# 24V_PWS.net
KiCad netlist of a schematic drawn in EAGLE
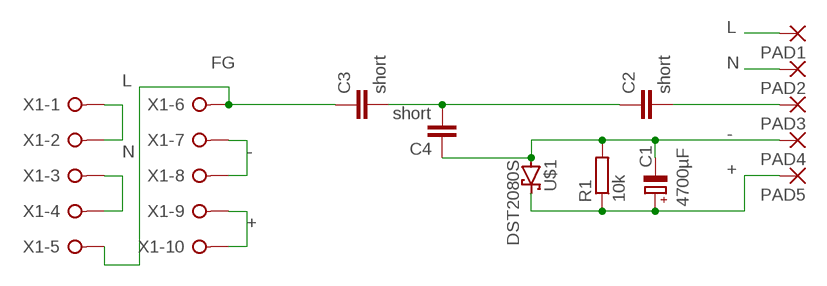
[diagram p0: schematic, sheet 1]

(export (version "E")
  (design (tool "Eeschema 10.0.6"))
  (components
    (comp (ref "C1")
      (value "4700µF")
      (footprint "eagle-import:E7,5-18")
      (libsource (lib "eagle-import") (part "CPOL-EUE7.5-18"))
    )
    (comp (ref "C2")
      (value "short")
      (footprint "eagle-import:C1206")
      (libsource (lib "eagle-import") (part "C-EUC1206"))
    )
    (comp (ref "C3")
      (value "short")
      (footprint "eagle-import:C1206")
      (libsource (lib "eagle-import") (part "C-EUC1206"))
    )
    (comp (ref "C4")
      (value "short")
      (footprint "eagle-import:C1206")
      (libsource (lib "eagle-import") (part "C-EUC1206"))
    )
    (comp (ref "PAD1")
      (value "SMD5")
      (footprint "eagle-import:SMD2,54-5,08")
      (libsource (lib "eagle-import") (part "SMD5"))
    )
    (comp (ref "PAD2")
      (value "SMD5")
      (footprint "eagle-import:SMD2,54-5,08")
      (libsource (lib "eagle-import") (part "SMD5"))
    )
    (comp (ref "PAD3")
      (value "SMD5")
      (footprint "eagle-import:SMD2,54-5,08")
      (libsource (lib "eagle-import") (part "SMD5"))
    )
    (comp (ref "PAD4")
      (value "SMD5")
      (footprint "eagle-import:SMD2,54-5,08")
      (libsource (lib "eagle-import") (part "SMD5"))
    )
    (comp (ref "PAD5")
      (value "SMD5")
      (footprint "eagle-import:SMD2,54-5,08")
      (libsource (lib "eagle-import") (part "SMD5"))
    )
    (comp (ref "R1")
      (value "10k")
      (footprint "eagle-import:R2012")
      (libsource (lib "eagle-import") (part "R-EU_R2012"))
    )
    (comp (ref "U$1")
      (value "DST2080S")
      (footprint "eagle-import:TO-277B")
      (libsource (lib "eagle-import") (part "DST2080S"))
    )
    (comp (ref "X1")
      (value "W237-10P")
      (footprint "eagle-import:W237-10P")
      (libsource (lib "eagle-import") (part "W237-10P"))
    )
  )
  (nets
    (net (code "1") (name "/+") (class "Default")
      (node (ref "C1") (pin "+") (pinfunction "+_+") (pintype "passive"))
      (node (ref "PAD5") (pin "1") (pinfunction "P_1") (pintype "passive"))
      (node (ref "R1") (pin "1") (pinfunction "1_1") (pintype "passive"))
      (node (ref "U$1") (pin "P$1") (pinfunction "C_P$1") (pintype "passive"))
      (node (ref "X1") (pin "10") (pinfunction "KL_10") (pintype "passive"))
      (node (ref "X1") (pin "9") (pinfunction "KL_9") (pintype "passive"))
    )
    (net (code "2") (name "/-") (class "Default")
      (node (ref "C1") (pin "-") (pinfunction "-_-") (pintype "passive"))
      (node (ref "C4") (pin "1") (pinfunction "1_1") (pintype "passive"))
      (node (ref "PAD4") (pin "1") (pinfunction "P_1") (pintype "passive"))
      (node (ref "R1") (pin "2") (pinfunction "2_2") (pintype "passive"))
      (node (ref "U$1") (pin "P$2") (pinfunction "A_P$2") (pintype "passive"))
      (node (ref "U$1") (pin "P$3") (pinfunction "A_P$3") (pintype "passive"))
      (node (ref "X1") (pin "7") (pinfunction "KL_7") (pintype "passive"))
      (node (ref "X1") (pin "8") (pinfunction "KL_8") (pintype "passive"))
    )
    (net (code "3") (name "/FG") (class "Default")
      (node (ref "C3") (pin "1") (pinfunction "1_1") (pintype "passive"))
      (node (ref "X1") (pin "5") (pinfunction "KL_5") (pintype "passive"))
      (node (ref "X1") (pin "6") (pinfunction "KL_6") (pintype "passive"))
    )
    (net (code "4") (name "/L") (class "Default")
      (node (ref "PAD1") (pin "1") (pinfunction "P_1") (pintype "passive"))
      (node (ref "X1") (pin "1") (pinfunction "KL_1") (pintype "passive"))
      (node (ref "X1") (pin "2") (pinfunction "KL_2") (pintype "passive"))
    )
    (net (code "5") (name "/N") (class "Default")
      (node (ref "PAD2") (pin "1") (pinfunction "P_1") (pintype "passive"))
      (node (ref "X1") (pin "3") (pinfunction "KL_3") (pintype "passive"))
      (node (ref "X1") (pin "4") (pinfunction "KL_4") (pintype "passive"))
    )
    (net (code "6") (name "Net-(C2-Pad1)") (class "Default")
      (node (ref "C2") (pin "1") (pinfunction "1_1") (pintype "passive"))
      (node (ref "C3") (pin "2") (pinfunction "2_2") (pintype "passive"))
      (node (ref "C4") (pin "2") (pinfunction "2_2") (pintype "passive"))
    )
    (net (code "7") (name "Net-(PAD3-P)") (class "Default")
      (node (ref "C2") (pin "2") (pinfunction "2_2") (pintype "passive"))
      (node (ref "PAD3") (pin "1") (pinfunction "P_1") (pintype "passive"))
    )
  )
)
